# Hlibok_PCB.net
KiCad netlist of a schematic drawn in EAGLE
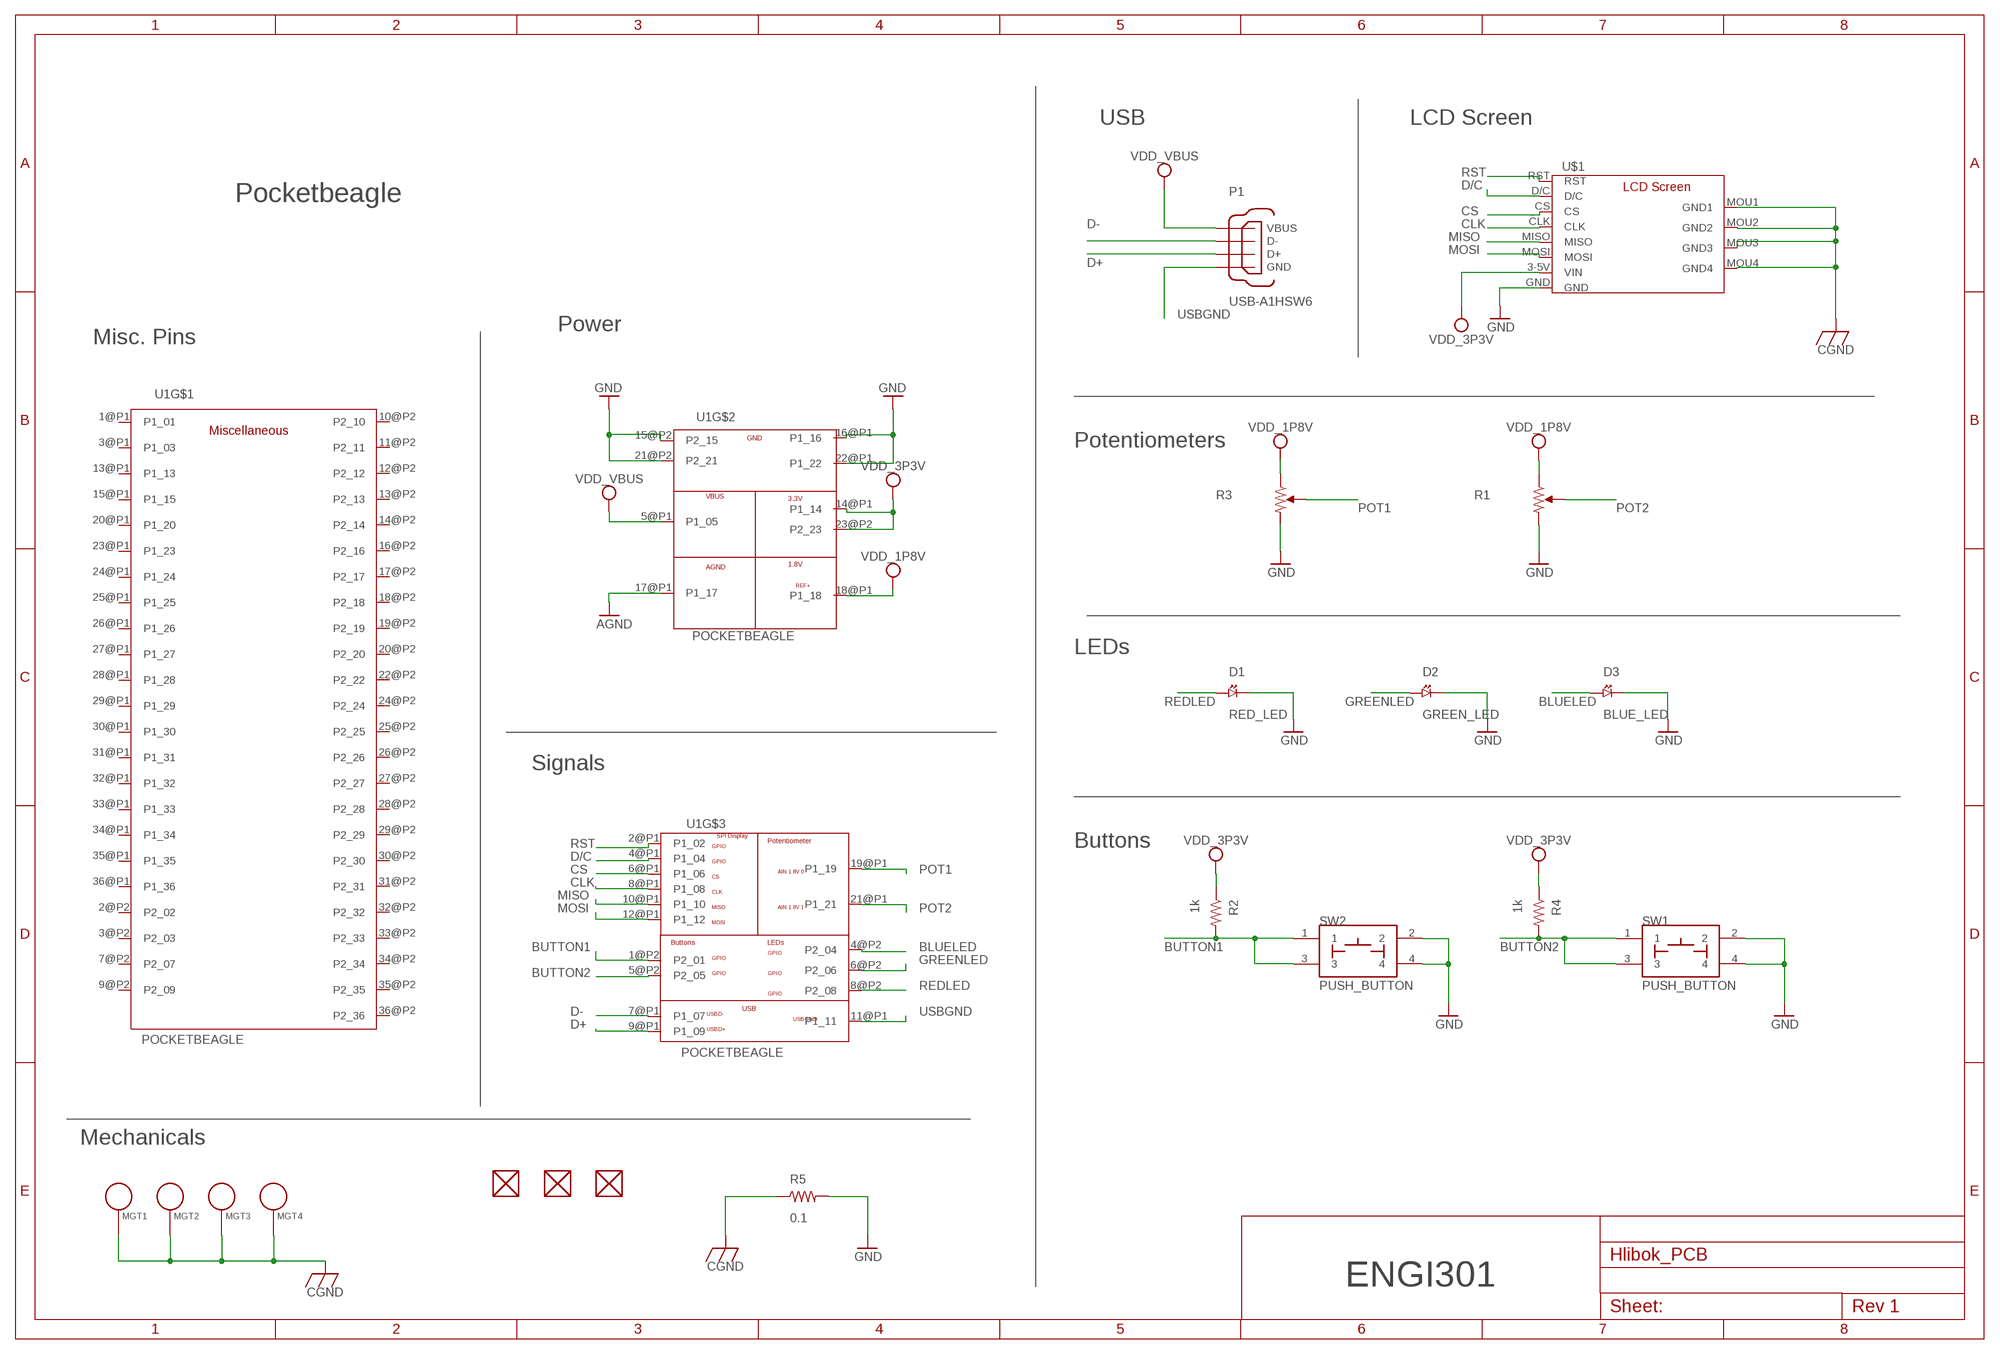
[diagram p0: schematic, sheet 1]

(export (version "E")
  (design (tool "Eeschema 10.0.6"))
  (components
    (comp (ref "D1")
      (value "RED_LED")
      (footprint "eagle-import:EIA-STD")
      (libsource (lib "eagle-import") (part "LED"))
    )
    (comp (ref "D2")
      (value "GREEN_LED")
      (footprint "eagle-import:EIA-STD")
      (libsource (lib "eagle-import") (part "LED"))
    )
    (comp (ref "D3")
      (value "BLUE_LED")
      (footprint "eagle-import:EIA-STD")
      (libsource (lib "eagle-import") (part "LED"))
    )
    (comp (ref "FUD1")
      (value "FIDUCIAL")
      (footprint "eagle-import:FIDUCIAL_40MIL")
      (libsource (lib "eagle-import") (part "FIDUCIAL"))
    )
    (comp (ref "FUD2")
      (value "FIDUCIAL")
      (footprint "eagle-import:FIDUCIAL_40MIL")
      (libsource (lib "eagle-import") (part "FIDUCIAL"))
    )
    (comp (ref "FUD3")
      (value "FIDUCIAL")
      (footprint "eagle-import:FIDUCIAL_40MIL")
      (libsource (lib "eagle-import") (part "FIDUCIAL"))
    )
    (comp (ref "MGT1")
      (value "MOUNTING_HOLE")
      (footprint "eagle-import:MOUNTING_HOLE")
      (libsource (lib "eagle-import") (part "MOUNTING_HOLE"))
    )
    (comp (ref "MGT2")
      (value "MOUNTING_HOLE")
      (footprint "eagle-import:MOUNTING_HOLE")
      (libsource (lib "eagle-import") (part "MOUNTING_HOLE"))
    )
    (comp (ref "MGT3")
      (value "MOUNTING_HOLE")
      (footprint "eagle-import:MOUNTING_HOLE")
      (libsource (lib "eagle-import") (part "MOUNTING_HOLE"))
    )
    (comp (ref "MGT4")
      (value "MOUNTING_HOLE")
      (footprint "eagle-import:MOUNTING_HOLE")
      (libsource (lib "eagle-import") (part "MOUNTING_HOLE"))
    )
    (comp (ref "P1")
      (value "USB-A1HSW6")
      (footprint "eagle-import:USB")
      (fields (field (name "MF") "On Shore"))
      (libsource (lib "eagle-import") (part "USB-A1HSW6"))
    )
    (comp (ref "R1")
      (value "POTENTIOMETER")
      (footprint "eagle-import:POT-PO90S")
      (libsource (lib "eagle-import") (part "POTENTIOMETER"))
    )
    (comp (ref "R2")
      (value "1k")
      (footprint "eagle-import:R0603")
      (libsource (lib "eagle-import") (part "R_R0603"))
    )
    (comp (ref "R3")
      (value "POTENTIOMETER")
      (footprint "eagle-import:POT-PO90S")
      (libsource (lib "eagle-import") (part "POTENTIOMETER"))
    )
    (comp (ref "R4")
      (value "1k")
      (footprint "eagle-import:R0603")
      (libsource (lib "eagle-import") (part "R_R0603"))
    )
    (comp (ref "R5")
      (value "0.1")
      (footprint "eagle-import:R0805")
      (libsource (lib "eagle-import") (part "R_R0805"))
    )
    (comp (ref "SW1")
      (value "PUSH_BUTTON")
      (footprint "eagle-import:BUTTON_12.5MM")
      (libsource (lib "eagle-import") (part "PUSH_BUTTON"))
    )
    (comp (ref "SW2")
      (value "PUSH_BUTTON")
      (footprint "eagle-import:BUTTON_12.5MM")
      (libsource (lib "eagle-import") (part "PUSH_BUTTON"))
    )
    (comp (ref "U$1")
      (value "SCREEN")
      (footprint "eagle-import:SCREEN")
      (libsource (lib "eagle-import") (part "SCREEN"))
    )
    (comp (ref "U1")
      (value "POCKETBEAGLE")
      (footprint "eagle-import:POCKETBEAGLE")
      (libsource (lib "eagle-import") (part "POCKETBEAGLE"))
    )
  )
  (nets
    (net (code "1") (name "/BLUELED") (class "Default")
      (node (ref "D3") (pin "ANODE") (pinfunction "ANODE_ANODE") (pintype "bidirectional"))
      (node (ref "U1") (pin "4@P2") (pinfunction "P2_04_4@P2") (pintype "bidirectional"))
    )
    (net (code "2") (name "/BUTTON1") (class "Default")
      (node (ref "R2") (pin "2") (pinfunction "2_2") (pintype "passive"))
      (node (ref "SW2") (pin "1") (pinfunction "1_1") (pintype "bidirectional"))
      (node (ref "SW2") (pin "3") (pinfunction "3_3") (pintype "bidirectional"))
      (node (ref "U1") (pin "1@P2") (pinfunction "P2_01_1@P2") (pintype "bidirectional"))
    )
    (net (code "3") (name "/BUTTON2") (class "Default")
      (node (ref "R4") (pin "2") (pinfunction "2_2") (pintype "passive"))
      (node (ref "SW1") (pin "1") (pinfunction "1_1") (pintype "bidirectional"))
      (node (ref "SW1") (pin "3") (pinfunction "3_3") (pintype "bidirectional"))
      (node (ref "U1") (pin "5@P2") (pinfunction "P2_05_5@P2") (pintype "bidirectional"))
    )
    (net (code "4") (name "/CLK") (class "Default")
      (node (ref "U$1") (pin "CLK") (pinfunction "CLK_CLK") (pintype "bidirectional"))
      (node (ref "U1") (pin "8@P1") (pinfunction "P1_08_8@P1") (pintype "bidirectional"))
    )
    (net (code "5") (name "/CS") (class "Default")
      (node (ref "U$1") (pin "CS") (pinfunction "CS_CS") (pintype "bidirectional"))
      (node (ref "U1") (pin "6@P1") (pinfunction "P1_06_6@P1") (pintype "bidirectional"))
    )
    (net (code "6") (name "/D+") (class "Default")
      (node (ref "P1") (pin "3") (pinfunction "D+_3") (pintype "bidirectional"))
      (node (ref "U1") (pin "9@P1") (pinfunction "P1_09_9@P1") (pintype "bidirectional"))
    )
    (net (code "7") (name "/D-") (class "Default")
      (node (ref "P1") (pin "2") (pinfunction "D-_2") (pintype "bidirectional"))
      (node (ref "U1") (pin "7@P1") (pinfunction "P1_07_7@P1") (pintype "bidirectional"))
    )
    (net (code "8") (name "/D{slash}C") (class "Default")
      (node (ref "U$1") (pin "D/C") (pinfunction "D/C_D/C") (pintype "bidirectional"))
      (node (ref "U1") (pin "4@P1") (pinfunction "P1_04_4@P1") (pintype "bidirectional"))
    )
    (net (code "9") (name "/GREENLED") (class "Default")
      (node (ref "D2") (pin "ANODE") (pinfunction "ANODE_ANODE") (pintype "bidirectional"))
      (node (ref "U1") (pin "6@P2") (pinfunction "P2_06_6@P2") (pintype "bidirectional"))
    )
    (net (code "10") (name "/MISO") (class "Default")
      (node (ref "U$1") (pin "MISO") (pinfunction "MISO_MISO") (pintype "bidirectional"))
      (node (ref "U1") (pin "10@P1") (pinfunction "P1_10_10@P1") (pintype "bidirectional"))
    )
    (net (code "11") (name "/MOSI") (class "Default")
      (node (ref "U$1") (pin "MOSI") (pinfunction "MOSI_MOSI") (pintype "bidirectional"))
      (node (ref "U1") (pin "12@P1") (pinfunction "P1_12_12@P1") (pintype "bidirectional"))
    )
    (net (code "12") (name "/POT1") (class "Default")
      (node (ref "R3") (pin "S") (pinfunction "S_S") (pintype "bidirectional"))
      (node (ref "U1") (pin "19@P1") (pinfunction "P1_19_19@P1") (pintype "bidirectional"))
    )
    (net (code "13") (name "/POT2") (class "Default")
      (node (ref "R1") (pin "S") (pinfunction "S_S") (pintype "bidirectional"))
      (node (ref "U1") (pin "21@P1") (pinfunction "P1_21_21@P1") (pintype "bidirectional"))
    )
    (net (code "14") (name "/REDLED") (class "Default")
      (node (ref "D1") (pin "ANODE") (pinfunction "ANODE_ANODE") (pintype "bidirectional"))
      (node (ref "U1") (pin "8@P2") (pinfunction "P2_08_8@P2") (pintype "bidirectional"))
    )
    (net (code "15") (name "/RST") (class "Default")
      (node (ref "U$1") (pin "RST") (pinfunction "RST_RST") (pintype "bidirectional"))
      (node (ref "U1") (pin "2@P1") (pinfunction "P1_02_2@P1") (pintype "bidirectional"))
    )
    (net (code "16") (name "/USBGND") (class "Default")
      (node (ref "P1") (pin "4") (pinfunction "GND_4") (pintype "power_in"))
      (node (ref "U1") (pin "11@P1") (pinfunction "P1_11_11@P1") (pintype "bidirectional"))
    )
    (net (code "17") (name "AGND") (class "Default")
      (node (ref "D1") (pin "CATHODE") (pinfunction "CATHODE_CATHODE") (pintype "bidirectional"))
      (node (ref "D2") (pin "CATHODE") (pinfunction "CATHODE_CATHODE") (pintype "bidirectional"))
      (node (ref "D3") (pin "CATHODE") (pinfunction "CATHODE_CATHODE") (pintype "bidirectional"))
      (node (ref "R1") (pin "CW") (pinfunction "CW_CW") (pintype "passive"))
      (node (ref "R3") (pin "CW") (pinfunction "CW_CW") (pintype "passive"))
      (node (ref "R5") (pin "2") (pinfunction "2_2") (pintype "passive"))
      (node (ref "SW1") (pin "2") (pinfunction "2_2") (pintype "bidirectional"))
      (node (ref "SW1") (pin "4") (pinfunction "4_4") (pintype "bidirectional"))
      (node (ref "SW2") (pin "2") (pinfunction "2_2") (pintype "bidirectional"))
      (node (ref "SW2") (pin "4") (pinfunction "4_4") (pintype "bidirectional"))
      (node (ref "U$1") (pin "GND") (pinfunction "GND_GND") (pintype "bidirectional"))
      (node (ref "U1") (pin "15@P2") (pinfunction "P2_15_15@P2") (pintype "bidirectional"))
      (node (ref "U1") (pin "16@P1") (pinfunction "P1_16_16@P1") (pintype "bidirectional"))
      (node (ref "U1") (pin "17@P1") (pinfunction "P1_17_17@P1") (pintype "bidirectional"))
      (node (ref "U1") (pin "21@P2") (pinfunction "P2_21_21@P2") (pintype "bidirectional"))
      (node (ref "U1") (pin "22@P1") (pinfunction "P1_22_22@P1") (pintype "bidirectional"))
    )
    (net (code "18") (name "CGND") (class "Default")
      (node (ref "MGT1") (pin "P$1") (pinfunction "P$1_P$1") (pintype "bidirectional"))
      (node (ref "MGT2") (pin "P$1") (pinfunction "P$1_P$1") (pintype "bidirectional"))
      (node (ref "MGT3") (pin "P$1") (pinfunction "P$1_P$1") (pintype "bidirectional"))
      (node (ref "MGT4") (pin "P$1") (pinfunction "P$1_P$1") (pintype "bidirectional"))
      (node (ref "R5") (pin "1") (pinfunction "1_1") (pintype "passive"))
      (node (ref "U$1") (pin "MOU1") (pinfunction "GND1_MOU1") (pintype "bidirectional"))
      (node (ref "U$1") (pin "MOU2") (pinfunction "GND2_MOU2") (pintype "bidirectional"))
      (node (ref "U$1") (pin "MOU3") (pinfunction "GND3_MOU3") (pintype "bidirectional"))
      (node (ref "U$1") (pin "MOU4") (pinfunction "GND4_MOU4") (pintype "bidirectional"))
    )
    (net (code "19") (name "VDD_1P8V") (class "Default")
      (node (ref "R1") (pin "CCW") (pinfunction "CCW_CCW") (pintype "passive"))
      (node (ref "R3") (pin "CCW") (pinfunction "CCW_CCW") (pintype "passive"))
      (node (ref "U1") (pin "18@P1") (pinfunction "P1_18_18@P1") (pintype "bidirectional"))
    )
    (net (code "20") (name "VDD_3P3V") (class "Default")
      (node (ref "R2") (pin "1") (pinfunction "1_1") (pintype "passive"))
      (node (ref "R4") (pin "1") (pinfunction "1_1") (pintype "passive"))
      (node (ref "U$1") (pin "3-5V") (pinfunction "VIN_3-5V") (pintype "bidirectional"))
      (node (ref "U1") (pin "14@P1") (pinfunction "P1_14_14@P1") (pintype "bidirectional"))
      (node (ref "U1") (pin "23@P2") (pinfunction "P2_23_23@P2") (pintype "bidirectional"))
    )
    (net (code "21") (name "VDD_VBUS") (class "Default")
      (node (ref "P1") (pin "1") (pinfunction "VBUS_1") (pintype "power_in"))
      (node (ref "U1") (pin "5@P1") (pinfunction "P1_05_5@P1") (pintype "bidirectional"))
    )
    (net (code "22") (name "unconnected-(FUD1-PadP$1)") (class "Default")
      (node (ref "FUD1") (pin "P$1") (pinfunction "P$1_P$1") (pintype "no_connect"))
    )
    (net (code "23") (name "unconnected-(FUD2-PadP$1)") (class "Default")
      (node (ref "FUD2") (pin "P$1") (pinfunction "P$1_P$1") (pintype "no_connect"))
    )
    (net (code "24") (name "unconnected-(FUD3-PadP$1)") (class "Default")
      (node (ref "FUD3") (pin "P$1") (pinfunction "P$1_P$1") (pintype "no_connect"))
    )
    (net (code "25") (name "unconnected-(U1A-P1_01-Pad1@P1)") (class "Default")
      (node (ref "U1") (pin "1@P1") (pinfunction "P1_01_1@P1") (pintype "bidirectional"))
    )
    (net (code "26") (name "unconnected-(U1A-P1_03-Pad3@P1)") (class "Default")
      (node (ref "U1") (pin "3@P1") (pinfunction "P1_03_3@P1") (pintype "bidirectional"))
    )
    (net (code "27") (name "unconnected-(U1A-P1_13-Pad13@P1)") (class "Default")
      (node (ref "U1") (pin "13@P1") (pinfunction "P1_13_13@P1") (pintype "bidirectional"))
    )
    (net (code "28") (name "unconnected-(U1A-P1_15-Pad15@P1)") (class "Default")
      (node (ref "U1") (pin "15@P1") (pinfunction "P1_15_15@P1") (pintype "bidirectional"))
    )
    (net (code "29") (name "unconnected-(U1A-P1_20-Pad20@P1)") (class "Default")
      (node (ref "U1") (pin "20@P1") (pinfunction "P1_20_20@P1") (pintype "bidirectional"))
    )
    (net (code "30") (name "unconnected-(U1A-P1_23-Pad23@P1)") (class "Default")
      (node (ref "U1") (pin "23@P1") (pinfunction "P1_23_23@P1") (pintype "bidirectional"))
    )
    (net (code "31") (name "unconnected-(U1A-P1_24-Pad24@P1)") (class "Default")
      (node (ref "U1") (pin "24@P1") (pinfunction "P1_24_24@P1") (pintype "bidirectional"))
    )
    (net (code "32") (name "unconnected-(U1A-P1_25-Pad25@P1)") (class "Default")
      (node (ref "U1") (pin "25@P1") (pinfunction "P1_25_25@P1") (pintype "bidirectional"))
    )
    (net (code "33") (name "unconnected-(U1A-P1_26-Pad26@P1)") (class "Default")
      (node (ref "U1") (pin "26@P1") (pinfunction "P1_26_26@P1") (pintype "bidirectional"))
    )
    (net (code "34") (name "unconnected-(U1A-P1_27-Pad27@P1)") (class "Default")
      (node (ref "U1") (pin "27@P1") (pinfunction "P1_27_27@P1") (pintype "bidirectional"))
    )
    (net (code "35") (name "unconnected-(U1A-P1_28-Pad28@P1)") (class "Default")
      (node (ref "U1") (pin "28@P1") (pinfunction "P1_28_28@P1") (pintype "bidirectional"))
    )
    (net (code "36") (name "unconnected-(U1A-P1_29-Pad29@P1)") (class "Default")
      (node (ref "U1") (pin "29@P1") (pinfunction "P1_29_29@P1") (pintype "bidirectional"))
    )
    (net (code "37") (name "unconnected-(U1A-P1_30-Pad30@P1)") (class "Default")
      (node (ref "U1") (pin "30@P1") (pinfunction "P1_30_30@P1") (pintype "bidirectional"))
    )
    (net (code "38") (name "unconnected-(U1A-P1_31-Pad31@P1)") (class "Default")
      (node (ref "U1") (pin "31@P1") (pinfunction "P1_31_31@P1") (pintype "bidirectional"))
    )
    (net (code "39") (name "unconnected-(U1A-P1_32-Pad32@P1)") (class "Default")
      (node (ref "U1") (pin "32@P1") (pinfunction "P1_32_32@P1") (pintype "bidirectional"))
    )
    (net (code "40") (name "unconnected-(U1A-P1_33-Pad33@P1)") (class "Default")
      (node (ref "U1") (pin "33@P1") (pinfunction "P1_33_33@P1") (pintype "bidirectional"))
    )
    (net (code "41") (name "unconnected-(U1A-P1_34-Pad34@P1)") (class "Default")
      (node (ref "U1") (pin "34@P1") (pinfunction "P1_34_34@P1") (pintype "bidirectional"))
    )
    (net (code "42") (name "unconnected-(U1A-P1_35-Pad35@P1)") (class "Default")
      (node (ref "U1") (pin "35@P1") (pinfunction "P1_35_35@P1") (pintype "bidirectional"))
    )
    (net (code "43") (name "unconnected-(U1A-P1_36-Pad36@P1)") (class "Default")
      (node (ref "U1") (pin "36@P1") (pinfunction "P1_36_36@P1") (pintype "bidirectional"))
    )
    (net (code "44") (name "unconnected-(U1A-P2_02-Pad2@P2)") (class "Default")
      (node (ref "U1") (pin "2@P2") (pinfunction "P2_02_2@P2") (pintype "bidirectional"))
    )
    (net (code "45") (name "unconnected-(U1A-P2_03-Pad3@P2)") (class "Default")
      (node (ref "U1") (pin "3@P2") (pinfunction "P2_03_3@P2") (pintype "bidirectional"))
    )
    (net (code "46") (name "unconnected-(U1A-P2_07-Pad7@P2)") (class "Default")
      (node (ref "U1") (pin "7@P2") (pinfunction "P2_07_7@P2") (pintype "bidirectional"))
    )
    (net (code "47") (name "unconnected-(U1A-P2_09-Pad9@P2)") (class "Default")
      (node (ref "U1") (pin "9@P2") (pinfunction "P2_09_9@P2") (pintype "bidirectional"))
    )
    (net (code "48") (name "unconnected-(U1A-P2_10-Pad10@P2)") (class "Default")
      (node (ref "U1") (pin "10@P2") (pinfunction "P2_10_10@P2") (pintype "bidirectional"))
    )
    (net (code "49") (name "unconnected-(U1A-P2_11-Pad11@P2)") (class "Default")
      (node (ref "U1") (pin "11@P2") (pinfunction "P2_11_11@P2") (pintype "bidirectional"))
    )
    (net (code "50") (name "unconnected-(U1A-P2_12-Pad12@P2)") (class "Default")
      (node (ref "U1") (pin "12@P2") (pinfunction "P2_12_12@P2") (pintype "bidirectional"))
    )
    (net (code "51") (name "unconnected-(U1A-P2_13-Pad13@P2)") (class "Default")
      (node (ref "U1") (pin "13@P2") (pinfunction "P2_13_13@P2") (pintype "bidirectional"))
    )
    (net (code "52") (name "unconnected-(U1A-P2_14-Pad14@P2)") (class "Default")
      (node (ref "U1") (pin "14@P2") (pinfunction "P2_14_14@P2") (pintype "bidirectional"))
    )
    (net (code "53") (name "unconnected-(U1A-P2_16-Pad16@P2)") (class "Default")
      (node (ref "U1") (pin "16@P2") (pinfunction "P2_16_16@P2") (pintype "bidirectional"))
    )
    (net (code "54") (name "unconnected-(U1A-P2_17-Pad17@P2)") (class "Default")
      (node (ref "U1") (pin "17@P2") (pinfunction "P2_17_17@P2") (pintype "bidirectional"))
    )
    (net (code "55") (name "unconnected-(U1A-P2_18-Pad18@P2)") (class "Default")
      (node (ref "U1") (pin "18@P2") (pinfunction "P2_18_18@P2") (pintype "bidirectional"))
    )
    (net (code "56") (name "unconnected-(U1A-P2_19-Pad19@P2)") (class "Default")
      (node (ref "U1") (pin "19@P2") (pinfunction "P2_19_19@P2") (pintype "bidirectional"))
    )
    (net (code "57") (name "unconnected-(U1A-P2_20-Pad20@P2)") (class "Default")
      (node (ref "U1") (pin "20@P2") (pinfunction "P2_20_20@P2") (pintype "bidirectional"))
    )
    (net (code "58") (name "unconnected-(U1A-P2_22-Pad22@P2)") (class "Default")
      (node (ref "U1") (pin "22@P2") (pinfunction "P2_22_22@P2") (pintype "bidirectional"))
    )
    (net (code "59") (name "unconnected-(U1A-P2_24-Pad24@P2)") (class "Default")
      (node (ref "U1") (pin "24@P2") (pinfunction "P2_24_24@P2") (pintype "bidirectional"))
    )
    (net (code "60") (name "unconnected-(U1A-P2_25-Pad25@P2)") (class "Default")
      (node (ref "U1") (pin "25@P2") (pinfunction "P2_25_25@P2") (pintype "bidirectional"))
    )
    (net (code "61") (name "unconnected-(U1A-P2_26-Pad26@P2)") (class "Default")
      (node (ref "U1") (pin "26@P2") (pinfunction "P2_26_26@P2") (pintype "bidirectional"))
    )
    (net (code "62") (name "unconnected-(U1A-P2_27-Pad27@P2)") (class "Default")
      (node (ref "U1") (pin "27@P2") (pinfunction "P2_27_27@P2") (pintype "bidirectional"))
    )
    (net (code "63") (name "unconnected-(U1A-P2_28-Pad28@P2)") (class "Default")
      (node (ref "U1") (pin "28@P2") (pinfunction "P2_28_28@P2") (pintype "bidirectional"))
    )
    (net (code "64") (name "unconnected-(U1A-P2_29-Pad29@P2)") (class "Default")
      (node (ref "U1") (pin "29@P2") (pinfunction "P2_29_29@P2") (pintype "bidirectional"))
    )
    (net (code "65") (name "unconnected-(U1A-P2_30-Pad30@P2)") (class "Default")
      (node (ref "U1") (pin "30@P2") (pinfunction "P2_30_30@P2") (pintype "bidirectional"))
    )
    (net (code "66") (name "unconnected-(U1A-P2_31-Pad31@P2)") (class "Default")
      (node (ref "U1") (pin "31@P2") (pinfunction "P2_31_31@P2") (pintype "bidirectional"))
    )
    (net (code "67") (name "unconnected-(U1A-P2_32-Pad32@P2)") (class "Default")
      (node (ref "U1") (pin "32@P2") (pinfunction "P2_32_32@P2") (pintype "bidirectional"))
    )
    (net (code "68") (name "unconnected-(U1A-P2_33-Pad33@P2)") (class "Default")
      (node (ref "U1") (pin "33@P2") (pinfunction "P2_33_33@P2") (pintype "bidirectional"))
    )
    (net (code "69") (name "unconnected-(U1A-P2_34-Pad34@P2)") (class "Default")
      (node (ref "U1") (pin "34@P2") (pinfunction "P2_34_34@P2") (pintype "bidirectional"))
    )
    (net (code "70") (name "unconnected-(U1A-P2_35-Pad35@P2)") (class "Default")
      (node (ref "U1") (pin "35@P2") (pinfunction "P2_35_35@P2") (pintype "bidirectional"))
    )
    (net (code "71") (name "unconnected-(U1A-P2_36-Pad36@P2)") (class "Default")
      (node (ref "U1") (pin "36@P2") (pinfunction "P2_36_36@P2") (pintype "bidirectional"))
    )
  )
)
